# lupa-breakout.net
KiCad netlist of a schematic drawn in EAGLE
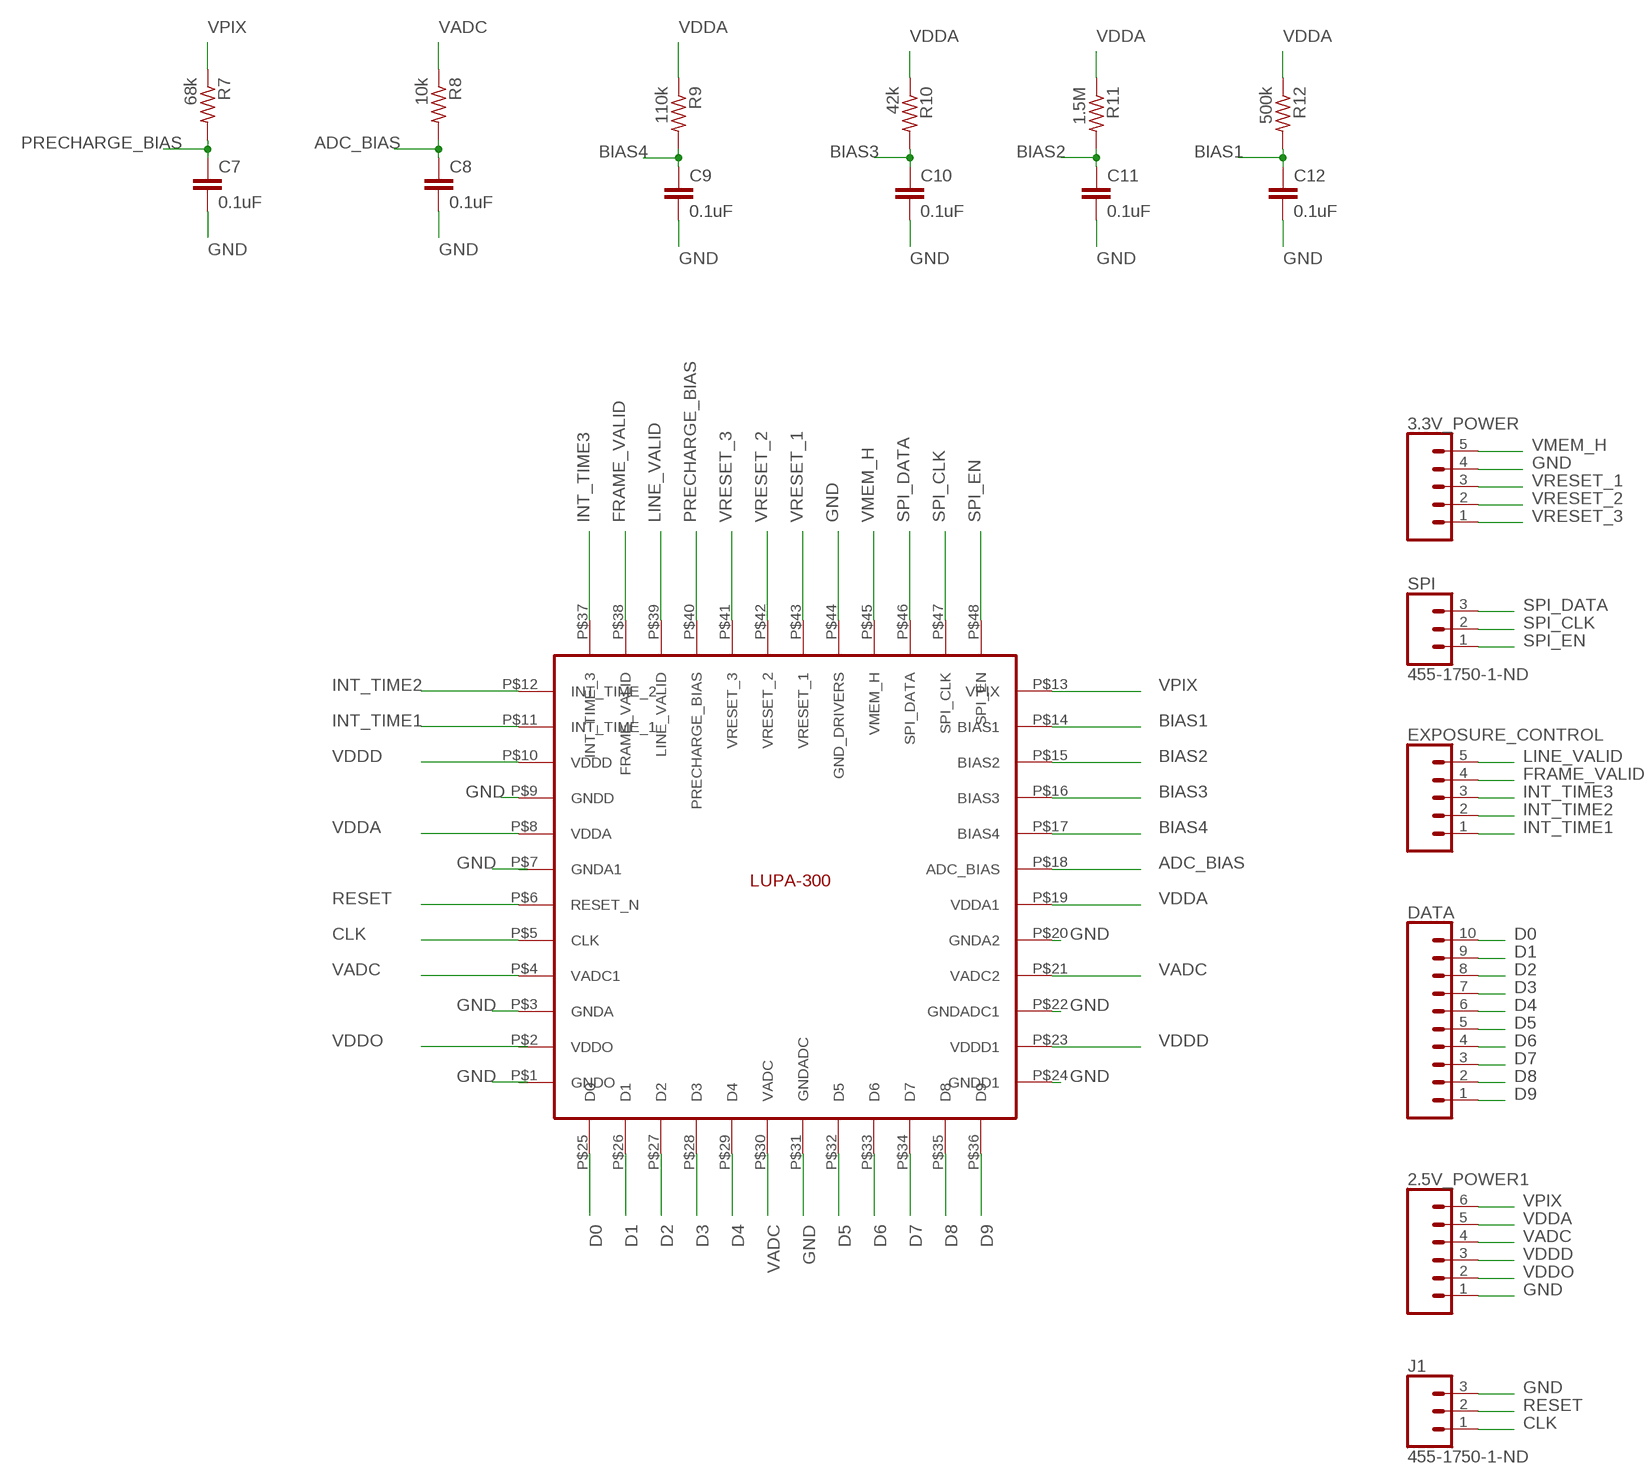
[diagram p0: schematic, sheet 1]

(export (version "E")
  (design (tool "Eeschema 10.0.6"))
  (components
    (comp (ref "2.5V_POWER1")
      (value "CONN_06SILK_FEMALE_PTH")
      (footprint "eagle-import:1X06")
      (libsource (lib "eagle-import") (part "CONN_06SILK_FEMALE_PTH"))
    )
    (comp (ref "3.3V_POWER")
      (value "CONN_05")
      (footprint "eagle-import:1X05")
      (libsource (lib "eagle-import") (part "CONN_05"))
    )
    (comp (ref "C7")
      (value "0.1uF")
      (footprint "eagle-import:C1206")
      (libsource (lib "eagle-import") (part "C-EUC1206"))
    )
    (comp (ref "C8")
      (value "0.1uF")
      (footprint "eagle-import:C1206")
      (libsource (lib "eagle-import") (part "C-EUC1206"))
    )
    (comp (ref "C9")
      (value "0.1uF")
      (footprint "eagle-import:C1206")
      (libsource (lib "eagle-import") (part "C-EUC1206"))
    )
    (comp (ref "C10")
      (value "0.1uF")
      (footprint "eagle-import:C1206")
      (libsource (lib "eagle-import") (part "C-EUC1206"))
    )
    (comp (ref "C11")
      (value "0.1uF")
      (footprint "eagle-import:C1206")
      (libsource (lib "eagle-import") (part "C-EUC1206"))
    )
    (comp (ref "C12")
      (value "0.1uF")
      (footprint "eagle-import:C1206")
      (libsource (lib "eagle-import") (part "C-EUC1206"))
    )
    (comp (ref "DATA")
      (value "CONN_10\"")
      (footprint "eagle-import:1X10")
      (libsource (lib "eagle-import") (part "CONN_10{dblquote}"))
    )
    (comp (ref "EXPOSURE_CONTROL")
      (value "CONN_05")
      (footprint "eagle-import:1X05")
      (libsource (lib "eagle-import") (part "CONN_05"))
    )
    (comp (ref "J1")
      (value "455-1750-1-ND")
      (footprint "eagle-import:1X03")
      (libsource (lib "eagle-import") (part "CONN_03"))
    )
    (comp (ref "R7")
      (value "68k")
      (footprint "eagle-import:M1206")
      (libsource (lib "eagle-import") (part "R-US_M1206"))
    )
    (comp (ref "R8")
      (value "10k")
      (footprint "eagle-import:M1206")
      (libsource (lib "eagle-import") (part "R-US_M1206"))
    )
    (comp (ref "R9")
      (value "110k")
      (footprint "eagle-import:M1206")
      (libsource (lib "eagle-import") (part "R-US_M1206"))
    )
    (comp (ref "R10")
      (value "42k")
      (footprint "eagle-import:M1206")
      (libsource (lib "eagle-import") (part "R-US_M1206"))
    )
    (comp (ref "R11")
      (value "1.5M")
      (footprint "eagle-import:M1206")
      (libsource (lib "eagle-import") (part "R-US_M1206"))
    )
    (comp (ref "R12")
      (value "500k")
      (footprint "eagle-import:M1206")
      (libsource (lib "eagle-import") (part "R-US_M1206"))
    )
    (comp (ref "SPI")
      (value "455-1750-1-ND")
      (footprint "eagle-import:1X03")
      (libsource (lib "eagle-import") (part "CONN_03"))
    )
    (comp (ref "U$1")
      (value "LUPA300")
      (footprint "eagle-import:LUPA300")
      (libsource (lib "eagle-import") (part "LUPA300"))
    )
  )
  (nets
    (net (code "1") (name "/ADC_BIAS") (class "Default")
      (node (ref "C8") (pin "1") (pinfunction "1_1") (pintype "passive"))
      (node (ref "R8") (pin "2") (pinfunction "2_2") (pintype "passive"))
      (node (ref "U$1") (pin "P$18") (pinfunction "ADC_BIAS_P$18") (pintype "bidirectional"))
    )
    (net (code "2") (name "/BIAS1") (class "Default")
      (node (ref "C12") (pin "1") (pinfunction "1_1") (pintype "passive"))
      (node (ref "R12") (pin "2") (pinfunction "2_2") (pintype "passive"))
      (node (ref "U$1") (pin "P$14") (pinfunction "BIAS1_P$14") (pintype "bidirectional"))
    )
    (net (code "3") (name "/BIAS2") (class "Default")
      (node (ref "C11") (pin "1") (pinfunction "1_1") (pintype "passive"))
      (node (ref "R11") (pin "2") (pinfunction "2_2") (pintype "passive"))
      (node (ref "U$1") (pin "P$15") (pinfunction "BIAS2_P$15") (pintype "bidirectional"))
    )
    (net (code "4") (name "/BIAS3") (class "Default")
      (node (ref "C10") (pin "1") (pinfunction "1_1") (pintype "passive"))
      (node (ref "R10") (pin "2") (pinfunction "2_2") (pintype "passive"))
      (node (ref "U$1") (pin "P$16") (pinfunction "BIAS3_P$16") (pintype "bidirectional"))
    )
    (net (code "5") (name "/BIAS4") (class "Default")
      (node (ref "C9") (pin "1") (pinfunction "1_1") (pintype "passive"))
      (node (ref "R9") (pin "2") (pinfunction "2_2") (pintype "passive"))
      (node (ref "U$1") (pin "P$17") (pinfunction "BIAS4_P$17") (pintype "bidirectional"))
    )
    (net (code "6") (name "/CLK") (class "Default")
      (node (ref "J1") (pin "1") (pinfunction "1_1") (pintype "passive"))
      (node (ref "U$1") (pin "P$5") (pinfunction "CLK_P$5") (pintype "bidirectional"))
    )
    (net (code "7") (name "/D0") (class "Default")
      (node (ref "DATA") (pin "10") (pinfunction "10_10") (pintype "passive"))
      (node (ref "U$1") (pin "P$25") (pinfunction "D0_P$25") (pintype "bidirectional"))
    )
    (net (code "8") (name "/D1") (class "Default")
      (node (ref "DATA") (pin "9") (pinfunction "9_9") (pintype "passive"))
      (node (ref "U$1") (pin "P$26") (pinfunction "D1_P$26") (pintype "bidirectional"))
    )
    (net (code "9") (name "/D2") (class "Default")
      (node (ref "DATA") (pin "8") (pinfunction "8_8") (pintype "passive"))
      (node (ref "U$1") (pin "P$27") (pinfunction "D2_P$27") (pintype "bidirectional"))
    )
    (net (code "10") (name "/D3") (class "Default")
      (node (ref "DATA") (pin "7") (pinfunction "7_7") (pintype "passive"))
      (node (ref "U$1") (pin "P$28") (pinfunction "D3_P$28") (pintype "bidirectional"))
    )
    (net (code "11") (name "/D4") (class "Default")
      (node (ref "DATA") (pin "6") (pinfunction "6_6") (pintype "passive"))
      (node (ref "U$1") (pin "P$29") (pinfunction "D4_P$29") (pintype "bidirectional"))
    )
    (net (code "12") (name "/D5") (class "Default")
      (node (ref "DATA") (pin "5") (pinfunction "5_5") (pintype "passive"))
      (node (ref "U$1") (pin "P$32") (pinfunction "D5_P$32") (pintype "bidirectional"))
    )
    (net (code "13") (name "/D6") (class "Default")
      (node (ref "DATA") (pin "4") (pinfunction "4_4") (pintype "passive"))
      (node (ref "U$1") (pin "P$33") (pinfunction "D6_P$33") (pintype "bidirectional"))
    )
    (net (code "14") (name "/D7") (class "Default")
      (node (ref "DATA") (pin "3") (pinfunction "3_3") (pintype "passive"))
      (node (ref "U$1") (pin "P$34") (pinfunction "D7_P$34") (pintype "bidirectional"))
    )
    (net (code "15") (name "/D8") (class "Default")
      (node (ref "DATA") (pin "2") (pinfunction "2_2") (pintype "passive"))
      (node (ref "U$1") (pin "P$35") (pinfunction "D8_P$35") (pintype "bidirectional"))
    )
    (net (code "16") (name "/D9") (class "Default")
      (node (ref "DATA") (pin "1") (pinfunction "1_1") (pintype "passive"))
      (node (ref "U$1") (pin "P$36") (pinfunction "D9_P$36") (pintype "bidirectional"))
    )
    (net (code "17") (name "/FRAME_VALID") (class "Default")
      (node (ref "EXPOSURE_CONTROL") (pin "4") (pinfunction "4_4") (pintype "passive"))
      (node (ref "U$1") (pin "P$38") (pinfunction "FRAME_VALID_P$38") (pintype "bidirectional"))
    )
    (net (code "18") (name "/GND") (class "Default")
      (node (ref "2.5V_POWER1") (pin "1") (pinfunction "1_1") (pintype "passive"))
      (node (ref "3.3V_POWER") (pin "4") (pinfunction "4_4") (pintype "passive"))
      (node (ref "C10") (pin "2") (pinfunction "2_2") (pintype "passive"))
      (node (ref "C11") (pin "2") (pinfunction "2_2") (pintype "passive"))
      (node (ref "C12") (pin "2") (pinfunction "2_2") (pintype "passive"))
      (node (ref "C7") (pin "2") (pinfunction "2_2") (pintype "passive"))
      (node (ref "C8") (pin "2") (pinfunction "2_2") (pintype "passive"))
      (node (ref "C9") (pin "2") (pinfunction "2_2") (pintype "passive"))
      (node (ref "J1") (pin "3") (pinfunction "3_3") (pintype "passive"))
      (node (ref "U$1") (pin "P$1") (pinfunction "GNDO_P$1") (pintype "bidirectional"))
      (node (ref "U$1") (pin "P$20") (pinfunction "GNDA2_P$20") (pintype "bidirectional"))
      (node (ref "U$1") (pin "P$22") (pinfunction "GNDADC1_P$22") (pintype "bidirectional"))
      (node (ref "U$1") (pin "P$24") (pinfunction "GNDD1_P$24") (pintype "bidirectional"))
      (node (ref "U$1") (pin "P$3") (pinfunction "GNDA_P$3") (pintype "bidirectional"))
      (node (ref "U$1") (pin "P$31") (pinfunction "GNDADC_P$31") (pintype "bidirectional"))
      (node (ref "U$1") (pin "P$44") (pinfunction "GND_DRIVERS_P$44") (pintype "bidirectional"))
      (node (ref "U$1") (pin "P$9") (pinfunction "GNDD_P$9") (pintype "bidirectional"))
    )
    (net (code "19") (name "/INT_TIME1") (class "Default")
      (node (ref "EXPOSURE_CONTROL") (pin "1") (pinfunction "1_1") (pintype "passive"))
      (node (ref "U$1") (pin "P$11") (pinfunction "INT_TIME_1_P$11") (pintype "bidirectional"))
    )
    (net (code "20") (name "/INT_TIME2") (class "Default")
      (node (ref "EXPOSURE_CONTROL") (pin "2") (pinfunction "2_2") (pintype "passive"))
      (node (ref "U$1") (pin "P$12") (pinfunction "INT_TIME_2_P$12") (pintype "bidirectional"))
    )
    (net (code "21") (name "/INT_TIME3") (class "Default")
      (node (ref "EXPOSURE_CONTROL") (pin "3") (pinfunction "3_3") (pintype "passive"))
      (node (ref "U$1") (pin "P$37") (pinfunction "INT_TIME_3_P$37") (pintype "bidirectional"))
    )
    (net (code "22") (name "/LINE_VALID") (class "Default")
      (node (ref "EXPOSURE_CONTROL") (pin "5") (pinfunction "5_5") (pintype "passive"))
      (node (ref "U$1") (pin "P$39") (pinfunction "LINE_VALID_P$39") (pintype "bidirectional"))
    )
    (net (code "23") (name "/PRECHARGE_BIAS") (class "Default")
      (node (ref "C7") (pin "1") (pinfunction "1_1") (pintype "passive"))
      (node (ref "R7") (pin "2") (pinfunction "2_2") (pintype "passive"))
      (node (ref "U$1") (pin "P$40") (pinfunction "PRECHARGE_BIAS_P$40") (pintype "bidirectional"))
    )
    (net (code "24") (name "/RESET") (class "Default")
      (node (ref "J1") (pin "2") (pinfunction "2_2") (pintype "passive"))
      (node (ref "U$1") (pin "P$6") (pinfunction "RESET_N_P$6") (pintype "bidirectional"))
    )
    (net (code "25") (name "/SPI_CLK") (class "Default")
      (node (ref "SPI") (pin "2") (pinfunction "2_2") (pintype "passive"))
      (node (ref "U$1") (pin "P$47") (pinfunction "SPI_CLK_P$47") (pintype "bidirectional"))
    )
    (net (code "26") (name "/SPI_DATA") (class "Default")
      (node (ref "SPI") (pin "3") (pinfunction "3_3") (pintype "passive"))
      (node (ref "U$1") (pin "P$46") (pinfunction "SPI_DATA_P$46") (pintype "bidirectional"))
    )
    (net (code "27") (name "/SPI_EN") (class "Default")
      (node (ref "SPI") (pin "1") (pinfunction "1_1") (pintype "passive"))
      (node (ref "U$1") (pin "P$48") (pinfunction "SPI_EN_P$48") (pintype "bidirectional"))
    )
    (net (code "28") (name "/VADC") (class "Default")
      (node (ref "2.5V_POWER1") (pin "4") (pinfunction "4_4") (pintype "passive"))
      (node (ref "R8") (pin "1") (pinfunction "1_1") (pintype "passive"))
      (node (ref "U$1") (pin "P$21") (pinfunction "VADC2_P$21") (pintype "bidirectional"))
      (node (ref "U$1") (pin "P$30") (pinfunction "VADC_P$30") (pintype "bidirectional"))
      (node (ref "U$1") (pin "P$4") (pinfunction "VADC1_P$4") (pintype "bidirectional"))
    )
    (net (code "29") (name "/VDDA") (class "Default")
      (node (ref "2.5V_POWER1") (pin "5") (pinfunction "5_5") (pintype "passive"))
      (node (ref "R10") (pin "1") (pinfunction "1_1") (pintype "passive"))
      (node (ref "R11") (pin "1") (pinfunction "1_1") (pintype "passive"))
      (node (ref "R12") (pin "1") (pinfunction "1_1") (pintype "passive"))
      (node (ref "R9") (pin "1") (pinfunction "1_1") (pintype "passive"))
      (node (ref "U$1") (pin "P$19") (pinfunction "VDDA1_P$19") (pintype "bidirectional"))
      (node (ref "U$1") (pin "P$8") (pinfunction "VDDA_P$8") (pintype "bidirectional"))
    )
    (net (code "30") (name "/VDDD") (class "Default")
      (node (ref "2.5V_POWER1") (pin "3") (pinfunction "3_3") (pintype "passive"))
      (node (ref "U$1") (pin "P$10") (pinfunction "VDDD_P$10") (pintype "bidirectional"))
      (node (ref "U$1") (pin "P$23") (pinfunction "VDDD1_P$23") (pintype "bidirectional"))
    )
    (net (code "31") (name "/VDDO") (class "Default")
      (node (ref "2.5V_POWER1") (pin "2") (pinfunction "2_2") (pintype "passive"))
      (node (ref "U$1") (pin "P$2") (pinfunction "VDDO_P$2") (pintype "bidirectional"))
    )
    (net (code "32") (name "/VMEM_H") (class "Default")
      (node (ref "3.3V_POWER") (pin "5") (pinfunction "5_5") (pintype "passive"))
      (node (ref "U$1") (pin "P$45") (pinfunction "VMEM_H_P$45") (pintype "bidirectional"))
    )
    (net (code "33") (name "/VPIX") (class "Default")
      (node (ref "2.5V_POWER1") (pin "6") (pinfunction "6_6") (pintype "passive"))
      (node (ref "R7") (pin "1") (pinfunction "1_1") (pintype "passive"))
      (node (ref "U$1") (pin "P$13") (pinfunction "VPIX_P$13") (pintype "bidirectional"))
    )
    (net (code "34") (name "/VRESET_1") (class "Default")
      (node (ref "3.3V_POWER") (pin "3") (pinfunction "3_3") (pintype "passive"))
      (node (ref "U$1") (pin "P$43") (pinfunction "VRESET_1_P$43") (pintype "bidirectional"))
    )
    (net (code "35") (name "/VRESET_2") (class "Default")
      (node (ref "3.3V_POWER") (pin "2") (pinfunction "2_2") (pintype "passive"))
      (node (ref "U$1") (pin "P$42") (pinfunction "VRESET_2_P$42") (pintype "bidirectional"))
    )
    (net (code "36") (name "/VRESET_3") (class "Default")
      (node (ref "3.3V_POWER") (pin "1") (pinfunction "1_1") (pintype "passive"))
      (node (ref "U$1") (pin "P$41") (pinfunction "VRESET_3_P$41") (pintype "bidirectional"))
    )
    (net (code "37") (name "unconnected-(U$1-GNDA1-PadP$7)") (class "Default")
      (node (ref "U$1") (pin "P$7") (pinfunction "GNDA1_P$7") (pintype "bidirectional"))
    )
  )
)
